# main.net
KiCad netlist of a schematic drawn in Altium Designer
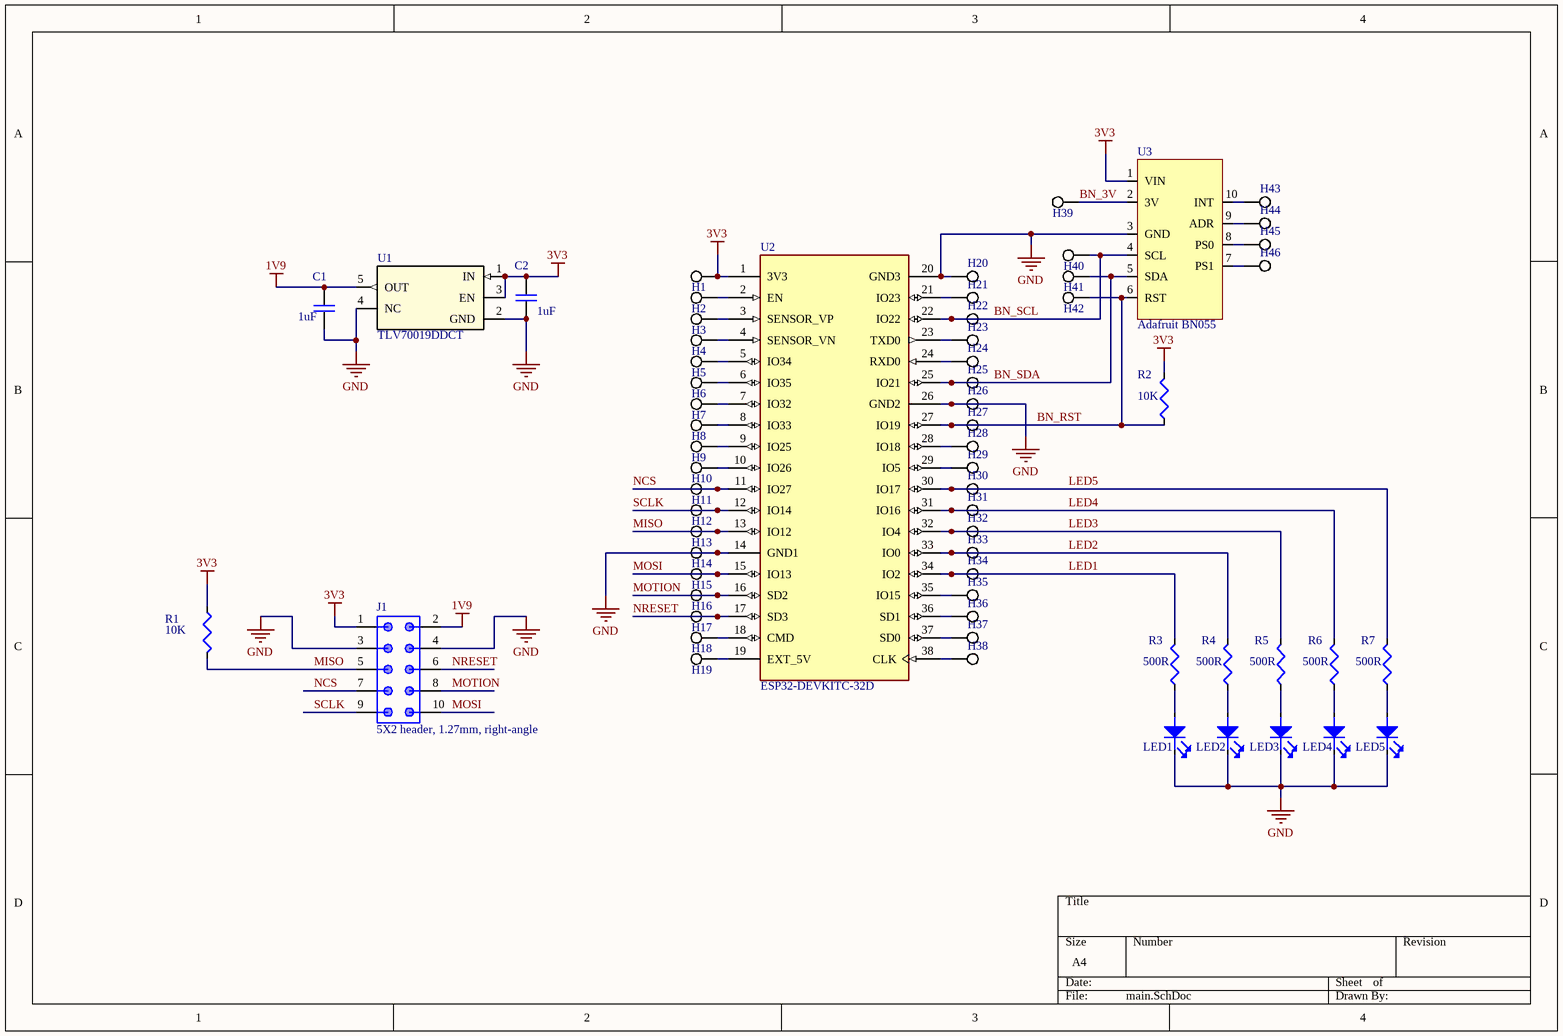
[diagram p0: main.SchDoc]

(export (version "E")
  (design (tool "Eeschema 10.0.6"))
  (components
    (comp (ref "C1")
      (value "1uF")
      (footprint "C0805")
      (description "C0805")
      (fields (field (name "Comment") "08053C105KAT2A"))
      (libsource (lib "Passive components") (part "08053C105KAT2A"))
    )
    (comp (ref "C2")
      (value "1uF")
      (footprint "C0805")
      (description "C0805")
      (fields (field (name "Comment") "08053C105KAT2A"))
      (libsource (lib "Passive components") (part "08053C105KAT2A"))
    )
    (comp (ref "H1")
      (value "Via prove-point/connection")
      (footprint "Hole")
      (libsource (lib "hub_card_schem_lib") (part "Hole"))
    )
    (comp (ref "H2")
      (value "Via prove-point/connection")
      (footprint "Hole")
      (libsource (lib "hub_card_schem_lib") (part "Hole"))
    )
    (comp (ref "H3")
      (value "Via prove-point/connection")
      (footprint "Hole")
      (libsource (lib "hub_card_schem_lib") (part "Hole"))
    )
    (comp (ref "H4")
      (value "Via prove-point/connection")
      (footprint "Hole")
      (libsource (lib "hub_card_schem_lib") (part "Hole"))
    )
    (comp (ref "H5")
      (value "Via prove-point/connection")
      (footprint "Hole")
      (libsource (lib "hub_card_schem_lib") (part "Hole"))
    )
    (comp (ref "H6")
      (value "Via prove-point/connection")
      (footprint "Hole")
      (libsource (lib "hub_card_schem_lib") (part "Hole"))
    )
    (comp (ref "H7")
      (value "Via prove-point/connection")
      (footprint "Hole")
      (libsource (lib "hub_card_schem_lib") (part "Hole"))
    )
    (comp (ref "H8")
      (value "Via prove-point/connection")
      (footprint "Hole")
      (libsource (lib "hub_card_schem_lib") (part "Hole"))
    )
    (comp (ref "H9")
      (value "Via prove-point/connection")
      (footprint "Hole")
      (libsource (lib "hub_card_schem_lib") (part "Hole"))
    )
    (comp (ref "H10")
      (value "Via prove-point/connection")
      (footprint "Hole")
      (libsource (lib "hub_card_schem_lib") (part "Hole"))
    )
    (comp (ref "H11")
      (value "Via prove-point/connection")
      (footprint "Hole")
      (libsource (lib "hub_card_schem_lib") (part "Hole"))
    )
    (comp (ref "H12")
      (value "Via prove-point/connection")
      (footprint "Hole")
      (libsource (lib "hub_card_schem_lib") (part "Hole"))
    )
    (comp (ref "H13")
      (value "Via prove-point/connection")
      (footprint "Hole")
      (libsource (lib "hub_card_schem_lib") (part "Hole"))
    )
    (comp (ref "H14")
      (value "Via prove-point/connection")
      (footprint "Hole")
      (libsource (lib "hub_card_schem_lib") (part "Hole"))
    )
    (comp (ref "H15")
      (value "Via prove-point/connection")
      (footprint "Hole")
      (libsource (lib "hub_card_schem_lib") (part "Hole"))
    )
    (comp (ref "H16")
      (value "Via prove-point/connection")
      (footprint "Hole")
      (libsource (lib "hub_card_schem_lib") (part "Hole"))
    )
    (comp (ref "H17")
      (value "Via prove-point/connection")
      (footprint "Hole")
      (libsource (lib "hub_card_schem_lib") (part "Hole"))
    )
    (comp (ref "H18")
      (value "Via prove-point/connection")
      (footprint "Hole")
      (libsource (lib "hub_card_schem_lib") (part "Hole"))
    )
    (comp (ref "H19")
      (value "Via prove-point/connection")
      (footprint "Hole")
      (libsource (lib "hub_card_schem_lib") (part "Hole"))
    )
    (comp (ref "H20")
      (value "Via prove-point/connection")
      (footprint "Hole")
      (libsource (lib "hub_card_schem_lib") (part "Hole"))
    )
    (comp (ref "H21")
      (value "Via prove-point/connection")
      (footprint "Hole")
      (libsource (lib "hub_card_schem_lib") (part "Hole"))
    )
    (comp (ref "H22")
      (value "Via prove-point/connection")
      (footprint "Hole")
      (libsource (lib "hub_card_schem_lib") (part "Hole"))
    )
    (comp (ref "H23")
      (value "Via prove-point/connection")
      (footprint "Hole")
      (libsource (lib "hub_card_schem_lib") (part "Hole"))
    )
    (comp (ref "H24")
      (value "Via prove-point/connection")
      (footprint "Hole")
      (libsource (lib "hub_card_schem_lib") (part "Hole"))
    )
    (comp (ref "H25")
      (value "Via prove-point/connection")
      (footprint "Hole")
      (libsource (lib "hub_card_schem_lib") (part "Hole"))
    )
    (comp (ref "H26")
      (value "Via prove-point/connection")
      (footprint "Hole")
      (libsource (lib "hub_card_schem_lib") (part "Hole"))
    )
    (comp (ref "H27")
      (value "Via prove-point/connection")
      (footprint "Hole")
      (libsource (lib "hub_card_schem_lib") (part "Hole"))
    )
    (comp (ref "H28")
      (value "Via prove-point/connection")
      (footprint "Hole")
      (libsource (lib "hub_card_schem_lib") (part "Hole"))
    )
    (comp (ref "H29")
      (value "Via prove-point/connection")
      (footprint "Hole")
      (libsource (lib "hub_card_schem_lib") (part "Hole"))
    )
    (comp (ref "H30")
      (value "Via prove-point/connection")
      (footprint "Hole")
      (libsource (lib "hub_card_schem_lib") (part "Hole"))
    )
    (comp (ref "H31")
      (value "Via prove-point/connection")
      (footprint "Hole")
      (libsource (lib "hub_card_schem_lib") (part "Hole"))
    )
    (comp (ref "H32")
      (value "Via prove-point/connection")
      (footprint "Hole")
      (libsource (lib "hub_card_schem_lib") (part "Hole"))
    )
    (comp (ref "H33")
      (value "Via prove-point/connection")
      (footprint "Hole")
      (libsource (lib "hub_card_schem_lib") (part "Hole"))
    )
    (comp (ref "H34")
      (value "Via prove-point/connection")
      (footprint "Hole")
      (libsource (lib "hub_card_schem_lib") (part "Hole"))
    )
    (comp (ref "H35")
      (value "Via prove-point/connection")
      (footprint "Hole")
      (libsource (lib "hub_card_schem_lib") (part "Hole"))
    )
    (comp (ref "H36")
      (value "Via prove-point/connection")
      (footprint "Hole")
      (libsource (lib "hub_card_schem_lib") (part "Hole"))
    )
    (comp (ref "H37")
      (value "Via prove-point/connection")
      (footprint "Hole")
      (libsource (lib "hub_card_schem_lib") (part "Hole"))
    )
    (comp (ref "H38")
      (value "Via prove-point/connection")
      (footprint "Hole")
      (libsource (lib "hub_card_schem_lib") (part "Hole"))
    )
    (comp (ref "H39")
      (value "Via prove-point/connection")
      (footprint "Hole")
      (libsource (lib "hub_card_schem_lib") (part "Hole"))
    )
    (comp (ref "H40")
      (value "Via prove-point/connection")
      (footprint "Hole")
      (libsource (lib "hub_card_schem_lib") (part "Hole"))
    )
    (comp (ref "H41")
      (value "Via prove-point/connection")
      (footprint "Hole")
      (libsource (lib "hub_card_schem_lib") (part "Hole"))
    )
    (comp (ref "H42")
      (value "Via prove-point/connection")
      (footprint "Hole")
      (libsource (lib "hub_card_schem_lib") (part "Hole"))
    )
    (comp (ref "H43")
      (value "Via prove-point/connection")
      (footprint "Hole")
      (libsource (lib "hub_card_schem_lib") (part "Hole"))
    )
    (comp (ref "H44")
      (value "Via prove-point/connection")
      (footprint "Hole")
      (libsource (lib "hub_card_schem_lib") (part "Hole"))
    )
    (comp (ref "H45")
      (value "Via prove-point/connection")
      (footprint "Hole")
      (libsource (lib "hub_card_schem_lib") (part "Hole"))
    )
    (comp (ref "H46")
      (value "Via prove-point/connection")
      (footprint "Hole")
      (libsource (lib "hub_card_schem_lib") (part "Hole"))
    )
    (comp (ref "J1")
      (value "5X2 header, 1.27mm, right-angle")
      (footprint "5X2 header, 1.27mm, right-angle")
      (libsource (lib "hub_card_schem_lib") (part "5X2 header, 1.27mm, right-angle"))
    )
    (comp (ref "LED1")
      (value "LED Blue")
      (footprint "L0603 BLUE")
      (description "LED 0603 Blue")
      (libsource (lib "Diodes") (part "HSMG-C199"))
    )
    (comp (ref "LED2")
      (value "LED Blue")
      (footprint "L0603 BLUE")
      (description "LED 0603 Blue")
      (libsource (lib "Diodes") (part "HSMG-C199"))
    )
    (comp (ref "LED3")
      (value "LED Blue")
      (footprint "L0603 BLUE")
      (description "LED 0603 Blue")
      (libsource (lib "Diodes") (part "HSMG-C199"))
    )
    (comp (ref "LED4")
      (value "LED Blue")
      (footprint "L0603 BLUE")
      (description "LED 0603 Blue")
      (libsource (lib "Diodes") (part "HSMG-C199"))
    )
    (comp (ref "LED5")
      (value "LED Blue")
      (footprint "L0603 BLUE")
      (description "LED 0603 Blue")
      (libsource (lib "Diodes") (part "HSMG-C199"))
    )
    (comp (ref "R1")
      (value "10K")
      (footprint "R0603")
      (description "R0603")
      (fields (field (name "Comment") "CPF-A-0603B100KE1"))
      (libsource (lib "PMW3389_SCHlib") (part "CPF-A-0603B100KE1"))
    )
    (comp (ref "R2")
      (value "10K")
      (footprint "R0603")
      (description "R0603")
      (fields (field (name "Comment") "CPF-A-0603B100KE1"))
      (libsource (lib "PMW3389_SCHlib") (part "CPF-A-0603B100KE1"))
    )
    (comp (ref "R3")
      (value "500R")
      (footprint "R0603")
      (description "R0603")
      (fields (field (name "Comment") "CPF-A-0603B100KE1"))
      (libsource (lib "PMW3389_SCHlib") (part "CPF-A-0603B100KE1"))
    )
    (comp (ref "R4")
      (value "500R")
      (footprint "R0603")
      (description "R0603")
      (fields (field (name "Comment") "CPF-A-0603B100KE1"))
      (libsource (lib "PMW3389_SCHlib") (part "CPF-A-0603B100KE1"))
    )
    (comp (ref "R5")
      (value "500R")
      (footprint "R0603")
      (description "R0603")
      (fields (field (name "Comment") "CPF-A-0603B100KE1"))
      (libsource (lib "PMW3389_SCHlib") (part "CPF-A-0603B100KE1"))
    )
    (comp (ref "R6")
      (value "500R")
      (footprint "R0603")
      (description "R0603")
      (fields (field (name "Comment") "CPF-A-0603B100KE1"))
      (libsource (lib "PMW3389_SCHlib") (part "CPF-A-0603B100KE1"))
    )
    (comp (ref "R7")
      (value "500R")
      (footprint "R0603")
      (description "R0603")
      (fields (field (name "Comment") "CPF-A-0603B100KE1"))
      (libsource (lib "PMW3389_SCHlib") (part "CPF-A-0603B100KE1"))
    )
    (comp (ref "U1")
      (value "TLV70019DDCT")
      (footprint "TLV70019DDCT")
      (libsource (lib "hub_card_schem_lib") (part "TLV70019DDCT"))
    )
    (comp (ref "U2")
      (value "ESP32-DEVKITC-32D")
      (footprint "ESP32")
      (description "ESP32-DEVKITC-32D module.")
      (libsource (lib "hub_card_schem_lib") (part "ESP32-DEVKITC-32D"))
    )
    (comp (ref "U3")
      (value "Adafruit BN055")
      (footprint "Adafruit BN055")
      (libsource (lib "hub_card_schem_lib") (part "Adafruit BN055"))
    )
  )
  (nets
    (net (code "1") (name "/BN_3V") (class "Default")
      (node (ref "H39") (pin "1") (pinfunction "1_1") (pintype "passive"))
      (node (ref "U3") (pin "2") (pinfunction "3V_2") (pintype "passive"))
    )
    (net (code "2") (name "/BN_RST") (class "Default")
      (node (ref "H27") (pin "1") (pinfunction "1_1") (pintype "passive"))
      (node (ref "H42") (pin "1") (pinfunction "1_1") (pintype "passive"))
      (node (ref "R2") (pin "1") (pinfunction "1_1") (pintype "passive"))
      (node (ref "U2") (pin "27") (pinfunction "IO19_27") (pintype "bidirectional"))
      (node (ref "U3") (pin "6") (pinfunction "RST_6") (pintype "passive"))
    )
    (net (code "3") (name "/BN_SCL") (class "Default")
      (node (ref "H22") (pin "1") (pinfunction "1_1") (pintype "passive"))
      (node (ref "H40") (pin "1") (pinfunction "1_1") (pintype "passive"))
      (node (ref "U2") (pin "22") (pinfunction "IO22_22") (pintype "bidirectional"))
      (node (ref "U3") (pin "4") (pinfunction "SCL_4") (pintype "passive"))
    )
    (net (code "4") (name "/BN_SDA") (class "Default")
      (node (ref "H25") (pin "1") (pinfunction "1_1") (pintype "passive"))
      (node (ref "H41") (pin "1") (pinfunction "1_1") (pintype "passive"))
      (node (ref "U2") (pin "25") (pinfunction "IO21_25") (pintype "bidirectional"))
      (node (ref "U3") (pin "5") (pinfunction "SDA_5") (pintype "passive"))
    )
    (net (code "5") (name "/LED1") (class "Default")
      (node (ref "H34") (pin "1") (pinfunction "1_1") (pintype "passive"))
      (node (ref "R3") (pin "2") (pinfunction "2_2") (pintype "passive"))
      (node (ref "U2") (pin "34") (pinfunction "IO2_34") (pintype "bidirectional"))
    )
    (net (code "6") (name "/LED2") (class "Default")
      (node (ref "H33") (pin "1") (pinfunction "1_1") (pintype "passive"))
      (node (ref "R4") (pin "2") (pinfunction "2_2") (pintype "passive"))
      (node (ref "U2") (pin "33") (pinfunction "IO0_33") (pintype "bidirectional"))
    )
    (net (code "7") (name "/LED3") (class "Default")
      (node (ref "H32") (pin "1") (pinfunction "1_1") (pintype "passive"))
      (node (ref "R5") (pin "2") (pinfunction "2_2") (pintype "passive"))
      (node (ref "U2") (pin "32") (pinfunction "IO4_32") (pintype "bidirectional"))
    )
    (net (code "8") (name "/LED4") (class "Default")
      (node (ref "H31") (pin "1") (pinfunction "1_1") (pintype "passive"))
      (node (ref "R6") (pin "2") (pinfunction "2_2") (pintype "passive"))
      (node (ref "U2") (pin "31") (pinfunction "IO16_31") (pintype "bidirectional"))
    )
    (net (code "9") (name "/LED5") (class "Default")
      (node (ref "H30") (pin "1") (pinfunction "1_1") (pintype "passive"))
      (node (ref "R7") (pin "2") (pinfunction "2_2") (pintype "passive"))
      (node (ref "U2") (pin "30") (pinfunction "IO17_30") (pintype "bidirectional"))
    )
    (net (code "10") (name "/MISO") (class "Default")
      (node (ref "H13") (pin "1") (pinfunction "1_1") (pintype "passive"))
      (node (ref "J1") (pin "5") (pinfunction "5_5") (pintype "passive"))
      (node (ref "R1") (pin "1") (pinfunction "1_1") (pintype "passive"))
      (node (ref "U2") (pin "13") (pinfunction "IO12_13") (pintype "bidirectional"))
    )
    (net (code "11") (name "/MOSI") (class "Default")
      (node (ref "H15") (pin "1") (pinfunction "1_1") (pintype "passive"))
      (node (ref "J1") (pin "10") (pinfunction "10_10") (pintype "passive"))
      (node (ref "U2") (pin "15") (pinfunction "IO13_15") (pintype "bidirectional"))
    )
    (net (code "12") (name "/MOTION") (class "Default")
      (node (ref "H16") (pin "1") (pinfunction "1_1") (pintype "passive"))
      (node (ref "J1") (pin "8") (pinfunction "8_8") (pintype "passive"))
      (node (ref "U2") (pin "16") (pinfunction "SD2_16") (pintype "bidirectional"))
    )
    (net (code "13") (name "/NCS") (class "Default")
      (node (ref "H11") (pin "1") (pinfunction "1_1") (pintype "passive"))
      (node (ref "J1") (pin "7") (pinfunction "7_7") (pintype "passive"))
      (node (ref "U2") (pin "11") (pinfunction "IO27_11") (pintype "bidirectional"))
    )
    (net (code "14") (name "/NRESET") (class "Default")
      (node (ref "H17") (pin "1") (pinfunction "1_1") (pintype "passive"))
      (node (ref "J1") (pin "6") (pinfunction "6_6") (pintype "passive"))
      (node (ref "U2") (pin "17") (pinfunction "SD3_17") (pintype "bidirectional"))
    )
    (net (code "15") (name "/SCLK") (class "Default")
      (node (ref "H12") (pin "1") (pinfunction "1_1") (pintype "passive"))
      (node (ref "J1") (pin "9") (pinfunction "9_9") (pintype "passive"))
      (node (ref "U2") (pin "12") (pinfunction "IO14_12") (pintype "bidirectional"))
    )
    (net (code "16") (name "1V9") (class "Default")
      (node (ref "C1") (pin "2") (pinfunction "2_2") (pintype "passive"))
      (node (ref "J1") (pin "2") (pinfunction "2_2") (pintype "passive"))
      (node (ref "U1") (pin "5") (pinfunction "OUT_5") (pintype "output"))
    )
    (net (code "17") (name "3V3") (class "Default")
      (node (ref "C2") (pin "2") (pinfunction "2_2") (pintype "passive"))
      (node (ref "H1") (pin "1") (pinfunction "1_1") (pintype "passive"))
      (node (ref "J1") (pin "1") (pinfunction "1_1") (pintype "passive"))
      (node (ref "R1") (pin "2") (pinfunction "2_2") (pintype "passive"))
      (node (ref "R2") (pin "2") (pinfunction "2_2") (pintype "passive"))
      (node (ref "U1") (pin "1") (pinfunction "IN_1") (pintype "input"))
      (node (ref "U1") (pin "3") (pinfunction "EN_3") (pintype "passive"))
      (node (ref "U2") (pin "1") (pinfunction "3V3_1") (pintype "power_in"))
      (node (ref "U3") (pin "1") (pinfunction "VIN_1") (pintype "passive"))
    )
    (net (code "18") (name "GND") (class "Default")
      (node (ref "C1") (pin "1") (pinfunction "1_1") (pintype "passive"))
      (node (ref "C2") (pin "1") (pinfunction "1_1") (pintype "passive"))
      (node (ref "H14") (pin "1") (pinfunction "1_1") (pintype "passive"))
      (node (ref "H20") (pin "1") (pinfunction "1_1") (pintype "passive"))
      (node (ref "H26") (pin "1") (pinfunction "1_1") (pintype "passive"))
      (node (ref "J1") (pin "3") (pinfunction "3_3") (pintype "passive"))
      (node (ref "J1") (pin "4") (pinfunction "4_4") (pintype "passive"))
      (node (ref "LED1") (pin "2") (pinfunction "2_2") (pintype "passive"))
      (node (ref "LED2") (pin "2") (pinfunction "2_2") (pintype "passive"))
      (node (ref "LED3") (pin "2") (pinfunction "2_2") (pintype "passive"))
      (node (ref "LED4") (pin "2") (pinfunction "2_2") (pintype "passive"))
      (node (ref "LED5") (pin "2") (pinfunction "2_2") (pintype "passive"))
      (node (ref "U1") (pin "2") (pinfunction "GND_2") (pintype "power_in"))
      (node (ref "U1") (pin "4") (pinfunction "NC_4") (pintype "passive"))
      (node (ref "U2") (pin "14") (pinfunction "GND1_14") (pintype "power_in"))
      (node (ref "U2") (pin "20") (pinfunction "GND3_20") (pintype "power_in"))
      (node (ref "U2") (pin "26") (pinfunction "GND2_26") (pintype "power_in"))
      (node (ref "U3") (pin "3") (pinfunction "GND_3") (pintype "passive"))
    )
    (net (code "19") (name "Net-(LED1-Pad1)") (class "Default")
      (node (ref "LED1") (pin "1") (pinfunction "1_1") (pintype "passive"))
      (node (ref "R3") (pin "1") (pinfunction "1_1") (pintype "passive"))
    )
    (net (code "20") (name "Net-(LED2-Pad1)") (class "Default")
      (node (ref "LED2") (pin "1") (pinfunction "1_1") (pintype "passive"))
      (node (ref "R4") (pin "1") (pinfunction "1_1") (pintype "passive"))
    )
    (net (code "21") (name "Net-(LED3-Pad1)") (class "Default")
      (node (ref "LED3") (pin "1") (pinfunction "1_1") (pintype "passive"))
      (node (ref "R5") (pin "1") (pinfunction "1_1") (pintype "passive"))
    )
    (net (code "22") (name "Net-(LED4-Pad1)") (class "Default")
      (node (ref "LED4") (pin "1") (pinfunction "1_1") (pintype "passive"))
      (node (ref "R6") (pin "1") (pinfunction "1_1") (pintype "passive"))
    )
    (net (code "23") (name "Net-(LED5-Pad1)") (class "Default")
      (node (ref "LED5") (pin "1") (pinfunction "1_1") (pintype "passive"))
      (node (ref "R7") (pin "1") (pinfunction "1_1") (pintype "passive"))
    )
    (net (code "24") (name "Net-(U2-CLK)") (class "Default")
      (node (ref "H38") (pin "1") (pinfunction "1_1") (pintype "passive"))
      (node (ref "U2") (pin "38") (pinfunction "CLK_38") (pintype "input"))
    )
    (net (code "25") (name "Net-(U2-CMD)") (class "Default")
      (node (ref "H18") (pin "1") (pinfunction "1_1") (pintype "passive"))
      (node (ref "U2") (pin "18") (pinfunction "CMD_18") (pintype "bidirectional"))
    )
    (net (code "26") (name "Net-(U2-EN)") (class "Default")
      (node (ref "H2") (pin "1") (pinfunction "1_1") (pintype "passive"))
      (node (ref "U2") (pin "2") (pinfunction "EN_2") (pintype "input"))
    )
    (net (code "27") (name "Net-(U2-EXT_5V)") (class "Default")
      (node (ref "H19") (pin "1") (pinfunction "1_1") (pintype "passive"))
      (node (ref "U2") (pin "19") (pinfunction "EXT_5V_19") (pintype "power_in"))
    )
    (net (code "28") (name "Net-(U2-IO5)") (class "Default")
      (node (ref "H29") (pin "1") (pinfunction "1_1") (pintype "passive"))
      (node (ref "U2") (pin "29") (pinfunction "IO5_29") (pintype "bidirectional"))
    )
    (net (code "29") (name "Net-(U2-IO15)") (class "Default")
      (node (ref "H35") (pin "1") (pinfunction "1_1") (pintype "passive"))
      (node (ref "U2") (pin "35") (pinfunction "IO15_35") (pintype "bidirectional"))
    )
    (net (code "30") (name "Net-(U2-IO18)") (class "Default")
      (node (ref "H28") (pin "1") (pinfunction "1_1") (pintype "passive"))
      (node (ref "U2") (pin "28") (pinfunction "IO18_28") (pintype "bidirectional"))
    )
    (net (code "31") (name "Net-(U2-IO23)") (class "Default")
      (node (ref "H21") (pin "1") (pinfunction "1_1") (pintype "passive"))
      (node (ref "U2") (pin "21") (pinfunction "IO23_21") (pintype "bidirectional"))
    )
    (net (code "32") (name "Net-(U2-IO25)") (class "Default")
      (node (ref "H9") (pin "1") (pinfunction "1_1") (pintype "passive"))
      (node (ref "U2") (pin "9") (pinfunction "IO25_9") (pintype "bidirectional"))
    )
    (net (code "33") (name "Net-(U2-IO26)") (class "Default")
      (node (ref "H10") (pin "1") (pinfunction "1_1") (pintype "passive"))
      (node (ref "U2") (pin "10") (pinfunction "IO26_10") (pintype "bidirectional"))
    )
    (net (code "34") (name "Net-(U2-IO32)") (class "Default")
      (node (ref "H7") (pin "1") (pinfunction "1_1") (pintype "passive"))
      (node (ref "U2") (pin "7") (pinfunction "IO32_7") (pintype "bidirectional"))
    )
    (net (code "35") (name "Net-(U2-IO33)") (class "Default")
      (node (ref "H8") (pin "1") (pinfunction "1_1") (pintype "passive"))
      (node (ref "U2") (pin "8") (pinfunction "IO33_8") (pintype "bidirectional"))
    )
    (net (code "36") (name "Net-(U2-IO34)") (class "Default")
      (node (ref "H5") (pin "1") (pinfunction "1_1") (pintype "passive"))
      (node (ref "U2") (pin "5") (pinfunction "IO34_5") (pintype "bidirectional"))
    )
    (net (code "37") (name "Net-(U2-IO35)") (class "Default")
      (node (ref "H6") (pin "1") (pinfunction "1_1") (pintype "passive"))
      (node (ref "U2") (pin "6") (pinfunction "IO35_6") (pintype "bidirectional"))
    )
    (net (code "38") (name "Net-(U2-RXD0)") (class "Default")
      (node (ref "H24") (pin "1") (pinfunction "1_1") (pintype "passive"))
      (node (ref "U2") (pin "24") (pinfunction "RXD0_24") (pintype "input"))
    )
    (net (code "39") (name "Net-(U2-SD0)") (class "Default")
      (node (ref "H37") (pin "1") (pinfunction "1_1") (pintype "passive"))
      (node (ref "U2") (pin "37") (pinfunction "SD0_37") (pintype "bidirectional"))
    )
    (net (code "40") (name "Net-(U2-SD1)") (class "Default")
      (node (ref "H36") (pin "1") (pinfunction "1_1") (pintype "passive"))
      (node (ref "U2") (pin "36") (pinfunction "SD1_36") (pintype "bidirectional"))
    )
    (net (code "41") (name "Net-(U2-SENSOR_VN)") (class "Default")
      (node (ref "H4") (pin "1") (pinfunction "1_1") (pintype "passive"))
      (node (ref "U2") (pin "4") (pinfunction "SENSOR_VN_4") (pintype "input"))
    )
    (net (code "42") (name "Net-(U2-SENSOR_VP)") (class "Default")
      (node (ref "H3") (pin "1") (pinfunction "1_1") (pintype "passive"))
      (node (ref "U2") (pin "3") (pinfunction "SENSOR_VP_3") (pintype "input"))
    )
    (net (code "43") (name "Net-(U2-TXD0)") (class "Default")
      (node (ref "H23") (pin "1") (pinfunction "1_1") (pintype "passive"))
      (node (ref "U2") (pin "23") (pinfunction "TXD0_23") (pintype "output"))
    )
    (net (code "44") (name "Net-(U3-ADR)") (class "Default")
      (node (ref "H44") (pin "1") (pinfunction "1_1") (pintype "passive"))
      (node (ref "U3") (pin "9") (pinfunction "ADR_9") (pintype "passive"))
    )
    (net (code "45") (name "Net-(U3-INT)") (class "Default")
      (node (ref "H43") (pin "1") (pinfunction "1_1") (pintype "passive"))
      (node (ref "U3") (pin "10") (pinfunction "INT_10") (pintype "passive"))
    )
    (net (code "46") (name "Net-(U3-PS0)") (class "Default")
      (node (ref "H45") (pin "1") (pinfunction "1_1") (pintype "passive"))
      (node (ref "U3") (pin "8") (pinfunction "PS0_8") (pintype "passive"))
    )
    (net (code "47") (name "Net-(U3-PS1)") (class "Default")
      (node (ref "H46") (pin "1") (pinfunction "1_1") (pintype "passive"))
      (node (ref "U3") (pin "7") (pinfunction "PS1_7") (pintype "passive"))
    )
  )
)
